# Mini_Robot_PCB.net
KiCad netlist of a schematic drawn in EAGLE
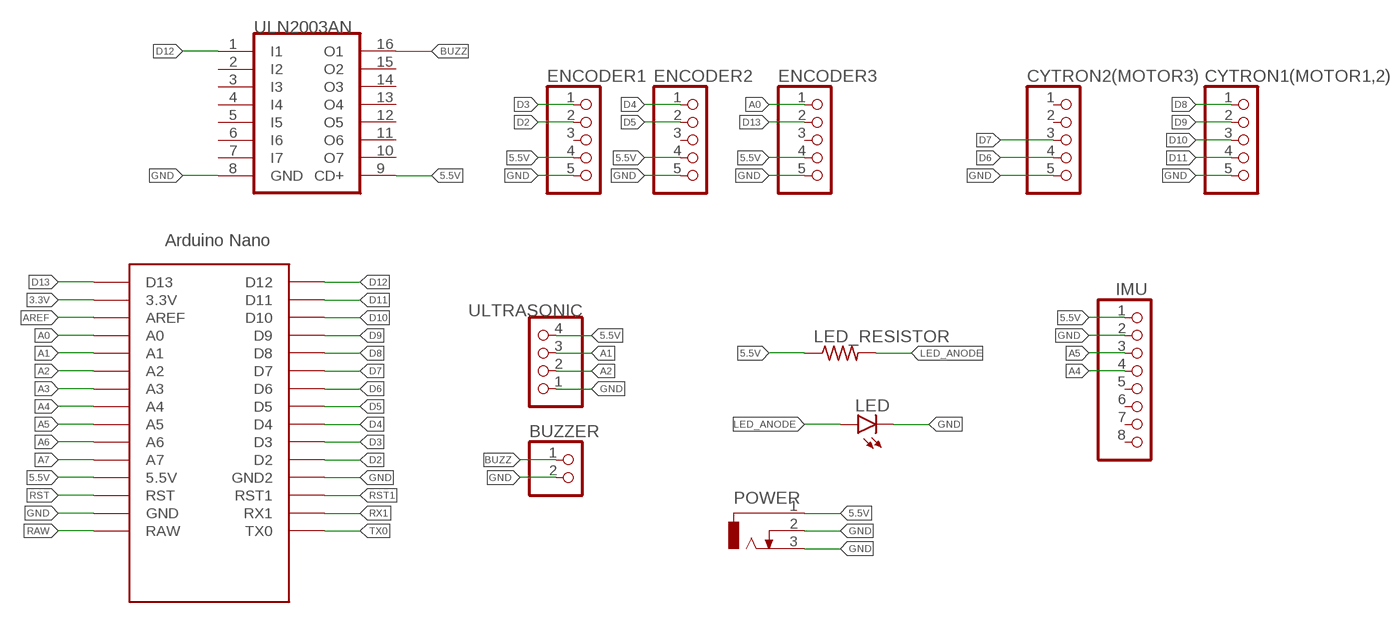
[diagram p0: schematic, sheet 1]

(export (version "E")
  (design (tool "Eeschema 10.0.6"))
  (components
    (comp (ref "BUZZER")
      (value "PINHD-1X2")
      (footprint "eagle-import:1X02")
      (libsource (lib "eagle-import") (part "PINHD-1X2"))
    )
    (comp (ref "CYTRON1(MOTOR1,2)")
      (value "PINHD-1X5")
      (footprint "eagle-import:1X05")
      (libsource (lib "eagle-import") (part "PINHD-1X5"))
    )
    (comp (ref "CYTRON2(MOTOR3)")
      (value "PINHD-1X5")
      (footprint "eagle-import:1X05")
      (libsource (lib "eagle-import") (part "PINHD-1X5"))
    )
    (comp (ref "ENCODER1")
      (value "PINHD-1X5")
      (footprint "eagle-import:1X05")
      (libsource (lib "eagle-import") (part "PINHD-1X5"))
    )
    (comp (ref "ENCODER2")
      (value "PINHD-1X5")
      (footprint "eagle-import:1X05")
      (libsource (lib "eagle-import") (part "PINHD-1X5"))
    )
    (comp (ref "ENCODER3")
      (value "PINHD-1X5")
      (footprint "eagle-import:1X05")
      (libsource (lib "eagle-import") (part "PINHD-1X5"))
    )
    (comp (ref "IC1")
      (value "ULN2003AN")
      (footprint "eagle-import:DIL16")
      (libsource (lib "eagle-import") (part "ULN2003AN"))
    )
    (comp (ref "IMU")
      (value "PINHD-1X8")
      (footprint "eagle-import:1X08")
      (libsource (lib "eagle-import") (part "PINHD-1X8"))
    )
    (comp (ref "LED")
      (value "LED5MM")
      (footprint "eagle-import:LED5MM")
      (libsource (lib "eagle-import") (part "LED5MM"))
    )
    (comp (ref "LED_RESISTOR")
      (value "RES-10")
      (footprint "eagle-import:0207_10")
      (libsource (lib "eagle-import") (part "RES-10"))
    )
    (comp (ref "POWER")
      (value "CON_JACK")
      (footprint "eagle-import:DCJ0303")
      (libsource (lib "eagle-import") (part "CON_JACK"))
    )
    (comp (ref "U$1")
      (value "ARDUINO_NANO")
      (footprint "eagle-import:NANO")
      (libsource (lib "eagle-import") (part "ARDUINO_NANO"))
    )
    (comp (ref "ULTRASONIC")
      (value "PINHD-1X4")
      (footprint "eagle-import:1X04")
      (libsource (lib "eagle-import") (part "PINHD-1X4"))
    )
  )
  (nets
    (net (code "1") (name "3.3V") (class "Default")
      (node (ref "U$1") (pin "3.3V") (pinfunction "3.3V_3.3V") (pintype "bidirectional"))
    )
    (net (code "2") (name "5.5V") (class "Default")
      (node (ref "ENCODER1") (pin "4") (pinfunction "4_4") (pintype "passive"))
      (node (ref "ENCODER2") (pin "4") (pinfunction "4_4") (pintype "passive"))
      (node (ref "ENCODER3") (pin "4") (pinfunction "4_4") (pintype "passive"))
      (node (ref "IC1") (pin "9") (pinfunction "CD+_9") (pintype "passive"))
      (node (ref "IMU") (pin "1") (pinfunction "1_1") (pintype "passive"))
      (node (ref "LED_RESISTOR") (pin "1") (pinfunction "1_1") (pintype "passive"))
      (node (ref "POWER") (pin "1") (pinfunction "1_1") (pintype "passive"))
      (node (ref "U$1") (pin "5V") (pinfunction "5.5V_5V") (pintype "bidirectional"))
      (node (ref "ULTRASONIC") (pin "4") (pinfunction "4_4") (pintype "passive"))
    )
    (net (code "3") (name "A0") (class "Default")
      (node (ref "ENCODER3") (pin "1") (pinfunction "1_1") (pintype "passive"))
      (node (ref "U$1") (pin "A0") (pinfunction "A0_A0") (pintype "bidirectional"))
    )
    (net (code "4") (name "A1") (class "Default")
      (node (ref "U$1") (pin "A1") (pinfunction "A1_A1") (pintype "bidirectional"))
      (node (ref "ULTRASONIC") (pin "3") (pinfunction "3_3") (pintype "passive"))
    )
    (net (code "5") (name "A2") (class "Default")
      (node (ref "U$1") (pin "A2") (pinfunction "A2_A2") (pintype "bidirectional"))
      (node (ref "ULTRASONIC") (pin "2") (pinfunction "2_2") (pintype "passive"))
    )
    (net (code "6") (name "A3") (class "Default")
      (node (ref "U$1") (pin "A3") (pinfunction "A3_A3") (pintype "bidirectional"))
    )
    (net (code "7") (name "A4") (class "Default")
      (node (ref "IMU") (pin "4") (pinfunction "4_4") (pintype "passive"))
      (node (ref "U$1") (pin "A4") (pinfunction "A4_A4") (pintype "bidirectional"))
    )
    (net (code "8") (name "A5") (class "Default")
      (node (ref "IMU") (pin "3") (pinfunction "3_3") (pintype "passive"))
      (node (ref "U$1") (pin "A5") (pinfunction "A5_A5") (pintype "bidirectional"))
    )
    (net (code "9") (name "A6") (class "Default")
      (node (ref "U$1") (pin "A6") (pinfunction "A6_A6") (pintype "bidirectional"))
    )
    (net (code "10") (name "A7") (class "Default")
      (node (ref "U$1") (pin "A7") (pinfunction "A7_A7") (pintype "bidirectional"))
    )
    (net (code "11") (name "AREF") (class "Default")
      (node (ref "U$1") (pin "AREF") (pinfunction "AREF_AREF") (pintype "bidirectional"))
    )
    (net (code "12") (name "BUZZ") (class "Default")
      (node (ref "BUZZER") (pin "1") (pinfunction "1_1") (pintype "passive"))
      (node (ref "IC1") (pin "16") (pinfunction "O1_16") (pintype "open_collector"))
    )
    (net (code "13") (name "D2") (class "Default")
      (node (ref "ENCODER1") (pin "2") (pinfunction "2_2") (pintype "passive"))
      (node (ref "U$1") (pin "D2") (pinfunction "D2_D2") (pintype "bidirectional"))
    )
    (net (code "14") (name "D3") (class "Default")
      (node (ref "ENCODER1") (pin "1") (pinfunction "1_1") (pintype "passive"))
      (node (ref "U$1") (pin "D3") (pinfunction "D3_D3") (pintype "bidirectional"))
    )
    (net (code "15") (name "D4") (class "Default")
      (node (ref "ENCODER2") (pin "1") (pinfunction "1_1") (pintype "passive"))
      (node (ref "U$1") (pin "D4") (pinfunction "D4_D4") (pintype "bidirectional"))
    )
    (net (code "16") (name "D5") (class "Default")
      (node (ref "ENCODER2") (pin "2") (pinfunction "2_2") (pintype "passive"))
      (node (ref "U$1") (pin "D5") (pinfunction "D5_D5") (pintype "bidirectional"))
    )
    (net (code "17") (name "D6") (class "Default")
      (node (ref "CYTRON2(MOTOR3)") (pin "4") (pinfunction "4_4") (pintype "passive"))
      (node (ref "U$1") (pin "D6") (pinfunction "D6_D6") (pintype "bidirectional"))
    )
    (net (code "18") (name "D7") (class "Default")
      (node (ref "CYTRON2(MOTOR3)") (pin "3") (pinfunction "3_3") (pintype "passive"))
      (node (ref "U$1") (pin "D7") (pinfunction "D7_D7") (pintype "bidirectional"))
    )
    (net (code "19") (name "D8") (class "Default")
      (node (ref "CYTRON1(MOTOR1,2)") (pin "1") (pinfunction "1_1") (pintype "passive"))
      (node (ref "U$1") (pin "D8") (pinfunction "D8_D8") (pintype "bidirectional"))
    )
    (net (code "20") (name "D9") (class "Default")
      (node (ref "CYTRON1(MOTOR1,2)") (pin "2") (pinfunction "2_2") (pintype "passive"))
      (node (ref "U$1") (pin "D9") (pinfunction "D9_D9") (pintype "bidirectional"))
    )
    (net (code "21") (name "D10") (class "Default")
      (node (ref "CYTRON1(MOTOR1,2)") (pin "3") (pinfunction "3_3") (pintype "passive"))
      (node (ref "U$1") (pin "D10") (pinfunction "D10_D10") (pintype "bidirectional"))
    )
    (net (code "22") (name "D11") (class "Default")
      (node (ref "CYTRON1(MOTOR1,2)") (pin "4") (pinfunction "4_4") (pintype "passive"))
      (node (ref "U$1") (pin "D11") (pinfunction "D11_D11") (pintype "bidirectional"))
    )
    (net (code "23") (name "D12") (class "Default")
      (node (ref "IC1") (pin "1") (pinfunction "I1_1") (pintype "input"))
      (node (ref "U$1") (pin "D12") (pinfunction "D12_D12") (pintype "bidirectional"))
    )
    (net (code "24") (name "D13") (class "Default")
      (node (ref "ENCODER3") (pin "2") (pinfunction "2_2") (pintype "passive"))
      (node (ref "U$1") (pin "D13") (pinfunction "D13_D13") (pintype "bidirectional"))
    )
    (net (code "25") (name "GND") (class "Default")
      (node (ref "BUZZER") (pin "2") (pinfunction "2_2") (pintype "passive"))
      (node (ref "CYTRON1(MOTOR1,2)") (pin "5") (pinfunction "5_5") (pintype "passive"))
      (node (ref "CYTRON2(MOTOR3)") (pin "5") (pinfunction "5_5") (pintype "passive"))
      (node (ref "ENCODER1") (pin "5") (pinfunction "5_5") (pintype "passive"))
      (node (ref "ENCODER2") (pin "5") (pinfunction "5_5") (pintype "passive"))
      (node (ref "ENCODER3") (pin "5") (pinfunction "5_5") (pintype "passive"))
      (node (ref "IC1") (pin "8") (pinfunction "GND_8") (pintype "power_in"))
      (node (ref "IMU") (pin "2") (pinfunction "2_2") (pintype "passive"))
      (node (ref "LED") (pin "K") (pinfunction "C_K") (pintype "passive"))
      (node (ref "POWER") (pin "2") (pinfunction "2_2") (pintype "passive"))
      (node (ref "POWER") (pin "3") (pinfunction "3_3") (pintype "passive"))
      (node (ref "U$1") (pin "GND") (pinfunction "GND_GND") (pintype "bidirectional"))
      (node (ref "U$1") (pin "GND1") (pinfunction "GND2_GND1") (pintype "bidirectional"))
      (node (ref "ULTRASONIC") (pin "1") (pinfunction "1_1") (pintype "passive"))
    )
    (net (code "26") (name "LED_ANODE") (class "Default")
      (node (ref "LED") (pin "A") (pinfunction "A_A") (pintype "passive"))
      (node (ref "LED_RESISTOR") (pin "2") (pinfunction "2_2") (pintype "passive"))
    )
    (net (code "27") (name "RAW") (class "Default")
      (node (ref "U$1") (pin "RAW") (pinfunction "RAW_RAW") (pintype "bidirectional"))
    )
    (net (code "28") (name "RST") (class "Default")
      (node (ref "U$1") (pin "RST") (pinfunction "RST_RST") (pintype "bidirectional"))
    )
    (net (code "29") (name "RST1") (class "Default")
      (node (ref "U$1") (pin "RST1") (pinfunction "RST1_RST1") (pintype "bidirectional"))
    )
    (net (code "30") (name "RX1") (class "Default")
      (node (ref "U$1") (pin "RX1") (pinfunction "RX1_RX1") (pintype "bidirectional"))
    )
    (net (code "31") (name "TX0") (class "Default")
      (node (ref "U$1") (pin "TX0") (pinfunction "TX0_TX0") (pintype "bidirectional"))
    )
    (net (code "32") (name "unconnected-(CYTRON2(MOTOR3)-Pad1)") (class "Default")
      (node (ref "CYTRON2(MOTOR3)") (pin "1") (pinfunction "1_1") (pintype "passive"))
    )
    (net (code "33") (name "unconnected-(CYTRON2(MOTOR3)-Pad2)") (class "Default")
      (node (ref "CYTRON2(MOTOR3)") (pin "2") (pinfunction "2_2") (pintype "passive"))
    )
    (net (code "34") (name "unconnected-(ENCODER1-Pad3)") (class "Default")
      (node (ref "ENCODER1") (pin "3") (pinfunction "3_3") (pintype "passive"))
    )
    (net (code "35") (name "unconnected-(ENCODER2-Pad3)") (class "Default")
      (node (ref "ENCODER2") (pin "3") (pinfunction "3_3") (pintype "passive"))
    )
    (net (code "36") (name "unconnected-(ENCODER3-Pad3)") (class "Default")
      (node (ref "ENCODER3") (pin "3") (pinfunction "3_3") (pintype "passive"))
    )
    (net (code "37") (name "unconnected-(IC1-I2-Pad2)") (class "Default")
      (node (ref "IC1") (pin "2") (pinfunction "I2_2") (pintype "input"))
    )
    (net (code "38") (name "unconnected-(IC1-I3-Pad3)") (class "Default")
      (node (ref "IC1") (pin "3") (pinfunction "I3_3") (pintype "input"))
    )
    (net (code "39") (name "unconnected-(IC1-I4-Pad4)") (class "Default")
      (node (ref "IC1") (pin "4") (pinfunction "I4_4") (pintype "input"))
    )
    (net (code "40") (name "unconnected-(IC1-I5-Pad5)") (class "Default")
      (node (ref "IC1") (pin "5") (pinfunction "I5_5") (pintype "input"))
    )
    (net (code "41") (name "unconnected-(IC1-I6-Pad6)") (class "Default")
      (node (ref "IC1") (pin "6") (pinfunction "I6_6") (pintype "input"))
    )
    (net (code "42") (name "unconnected-(IC1-I7-Pad7)") (class "Default")
      (node (ref "IC1") (pin "7") (pinfunction "I7_7") (pintype "input"))
    )
    (net (code "43") (name "unconnected-(IC1-O2-Pad15)") (class "Default")
      (node (ref "IC1") (pin "15") (pinfunction "O2_15") (pintype "open_collector"))
    )
    (net (code "44") (name "unconnected-(IC1-O3-Pad14)") (class "Default")
      (node (ref "IC1") (pin "14") (pinfunction "O3_14") (pintype "open_collector"))
    )
    (net (code "45") (name "unconnected-(IC1-O4-Pad13)") (class "Default")
      (node (ref "IC1") (pin "13") (pinfunction "O4_13") (pintype "open_collector"))
    )
    (net (code "46") (name "unconnected-(IC1-O5-Pad12)") (class "Default")
      (node (ref "IC1") (pin "12") (pinfunction "O5_12") (pintype "open_collector"))
    )
    (net (code "47") (name "unconnected-(IC1-O6-Pad11)") (class "Default")
      (node (ref "IC1") (pin "11") (pinfunction "O6_11") (pintype "open_collector"))
    )
    (net (code "48") (name "unconnected-(IC1-O7-Pad10)") (class "Default")
      (node (ref "IC1") (pin "10") (pinfunction "O7_10") (pintype "open_collector"))
    )
    (net (code "49") (name "unconnected-(IMU-Pad5)") (class "Default")
      (node (ref "IMU") (pin "5") (pinfunction "5_5") (pintype "passive"))
    )
    (net (code "50") (name "unconnected-(IMU-Pad6)") (class "Default")
      (node (ref "IMU") (pin "6") (pinfunction "6_6") (pintype "passive"))
    )
    (net (code "51") (name "unconnected-(IMU-Pad7)") (class "Default")
      (node (ref "IMU") (pin "7") (pinfunction "7_7") (pintype "passive"))
    )
    (net (code "52") (name "unconnected-(IMU-Pad8)") (class "Default")
      (node (ref "IMU") (pin "8") (pinfunction "8_8") (pintype "passive"))
    )
  )
)
